# 10LA_org_4PxU_RPi.net
KiCad netlist of a schematic drawn in EAGLE
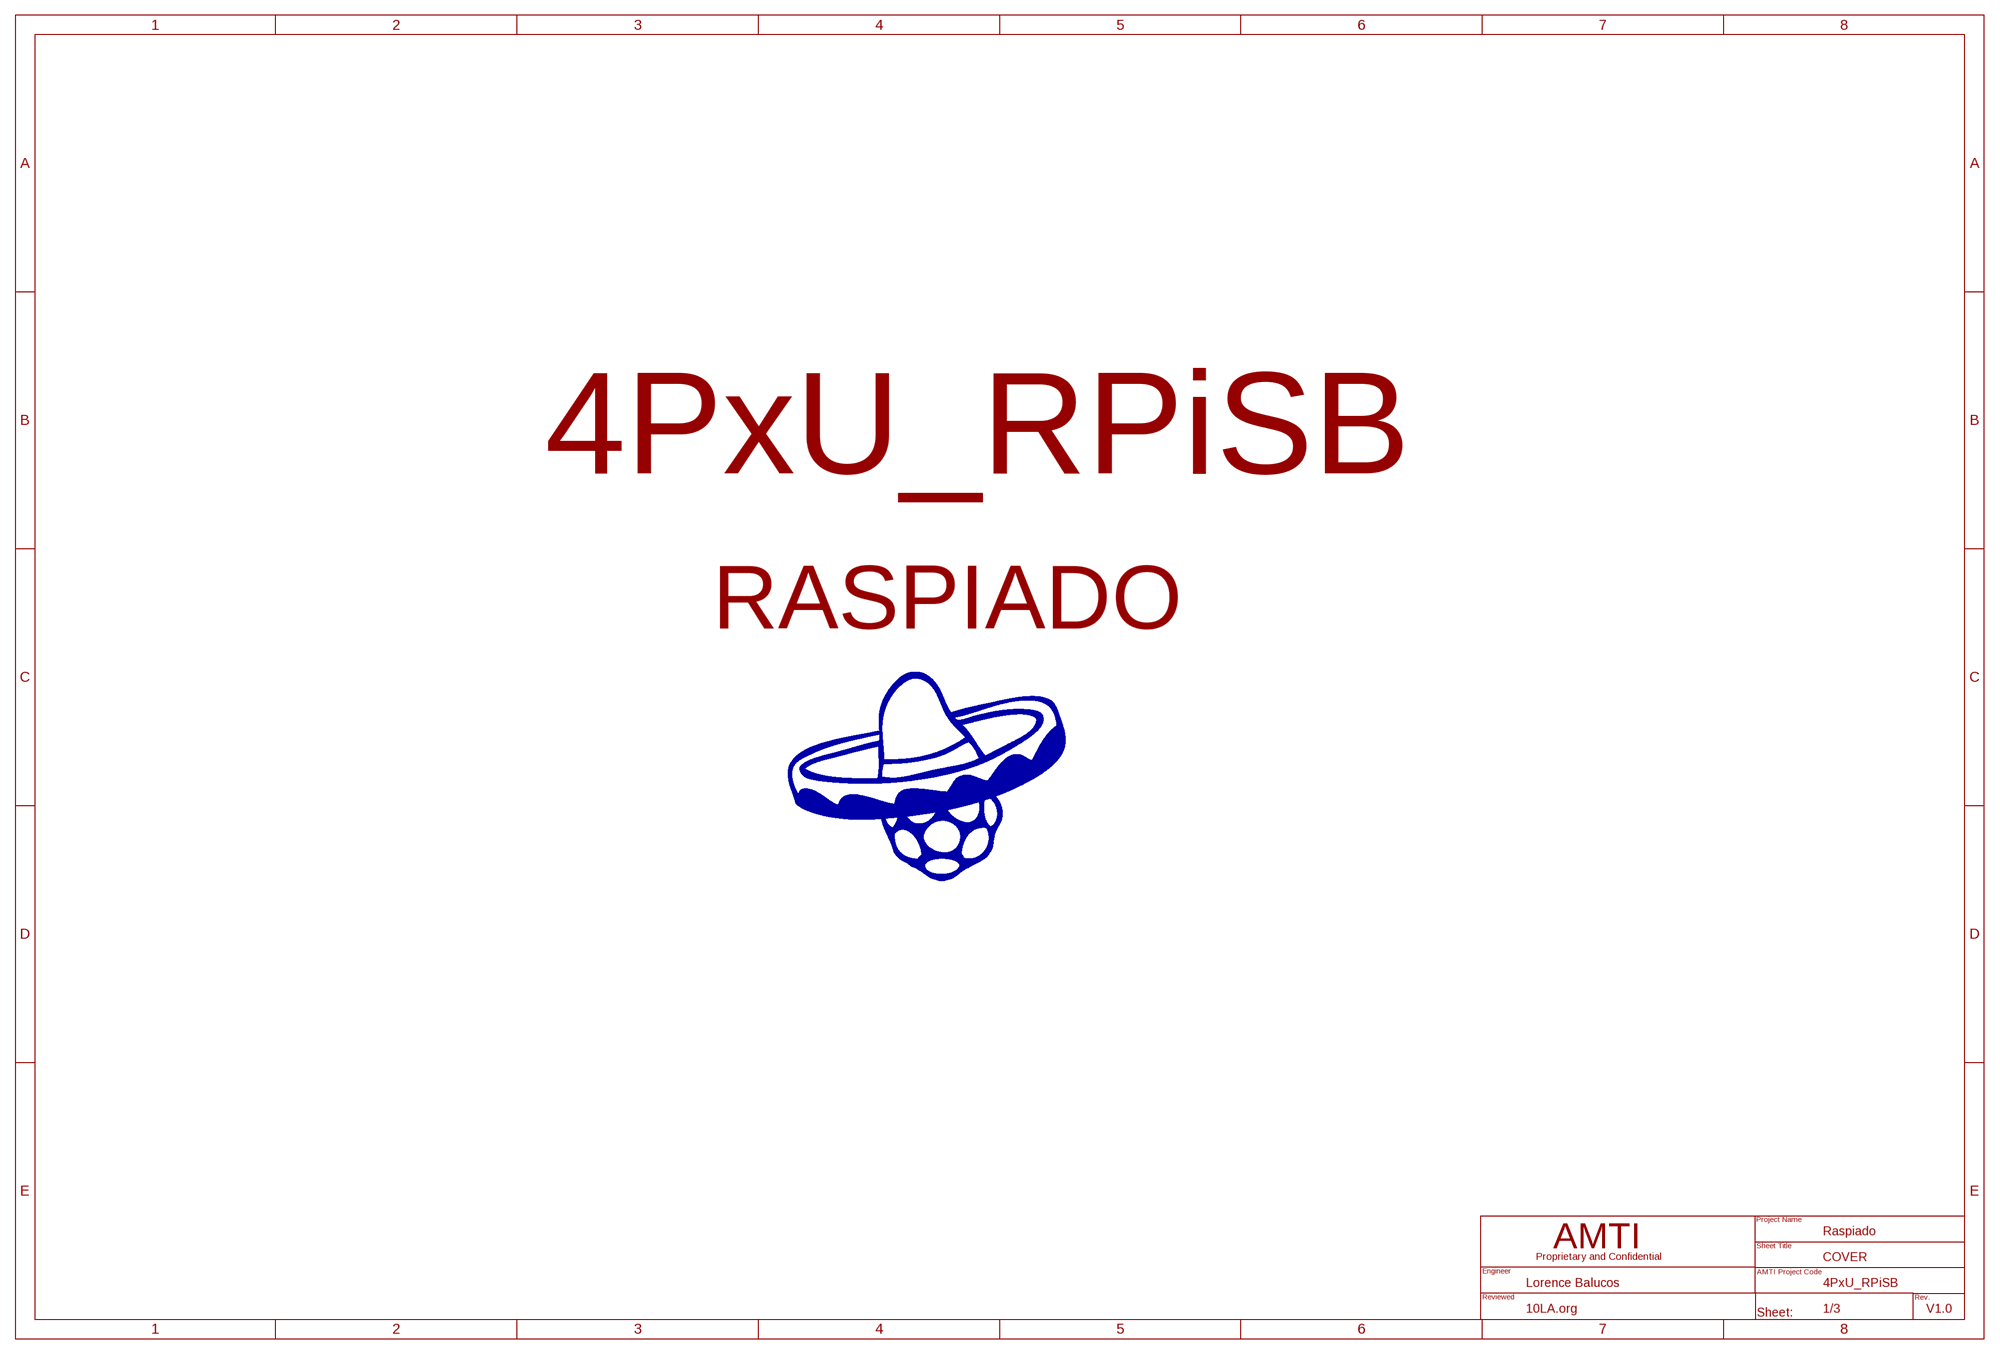
[diagram p0: schematic, sheet 1]
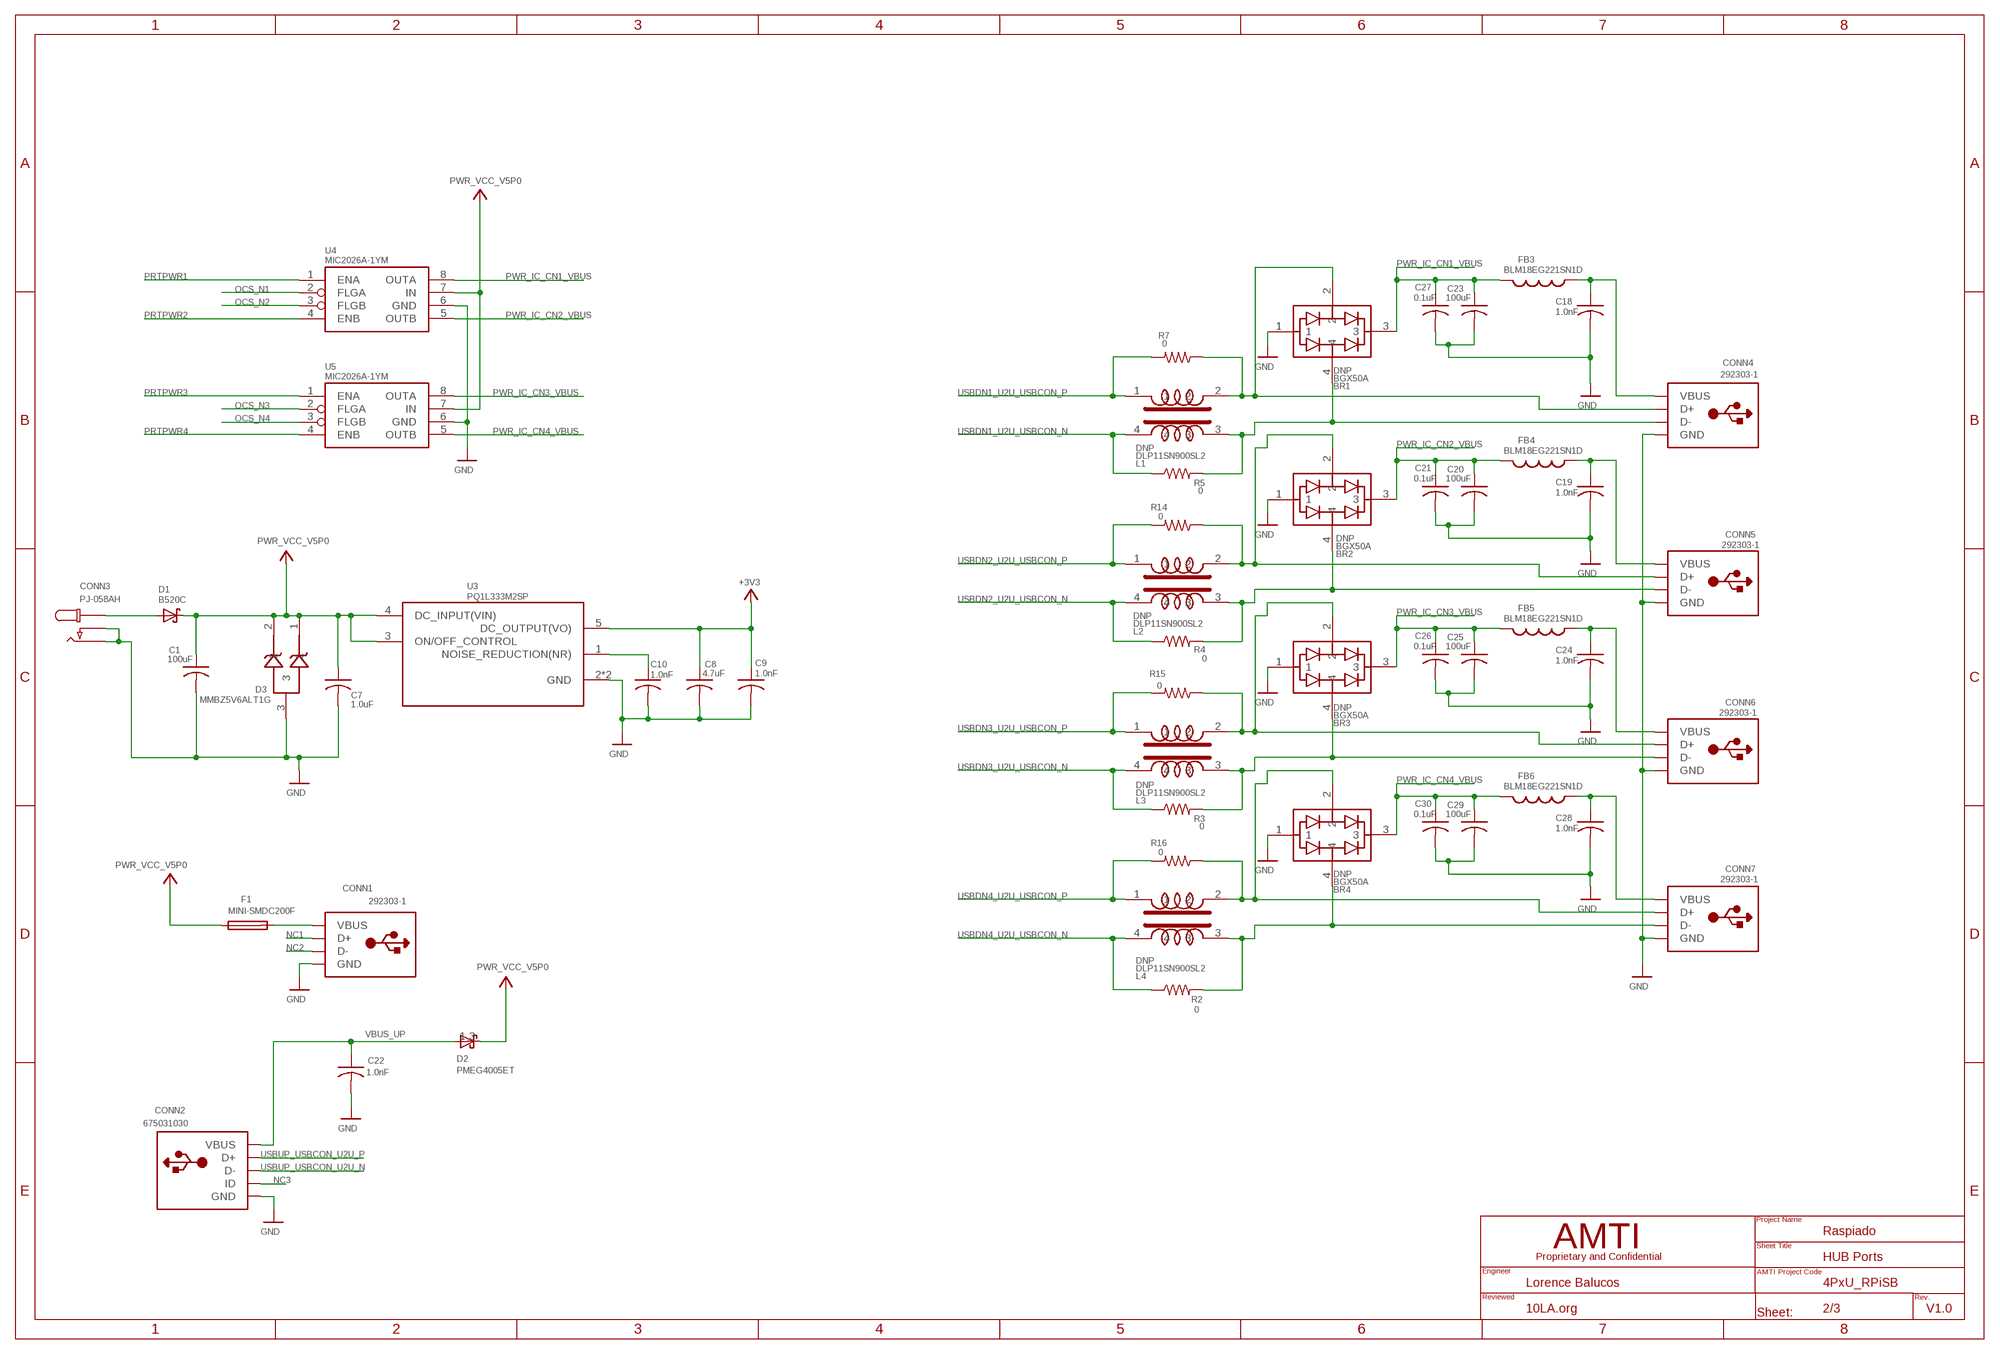
[diagram p1: schematic, sheet 2]
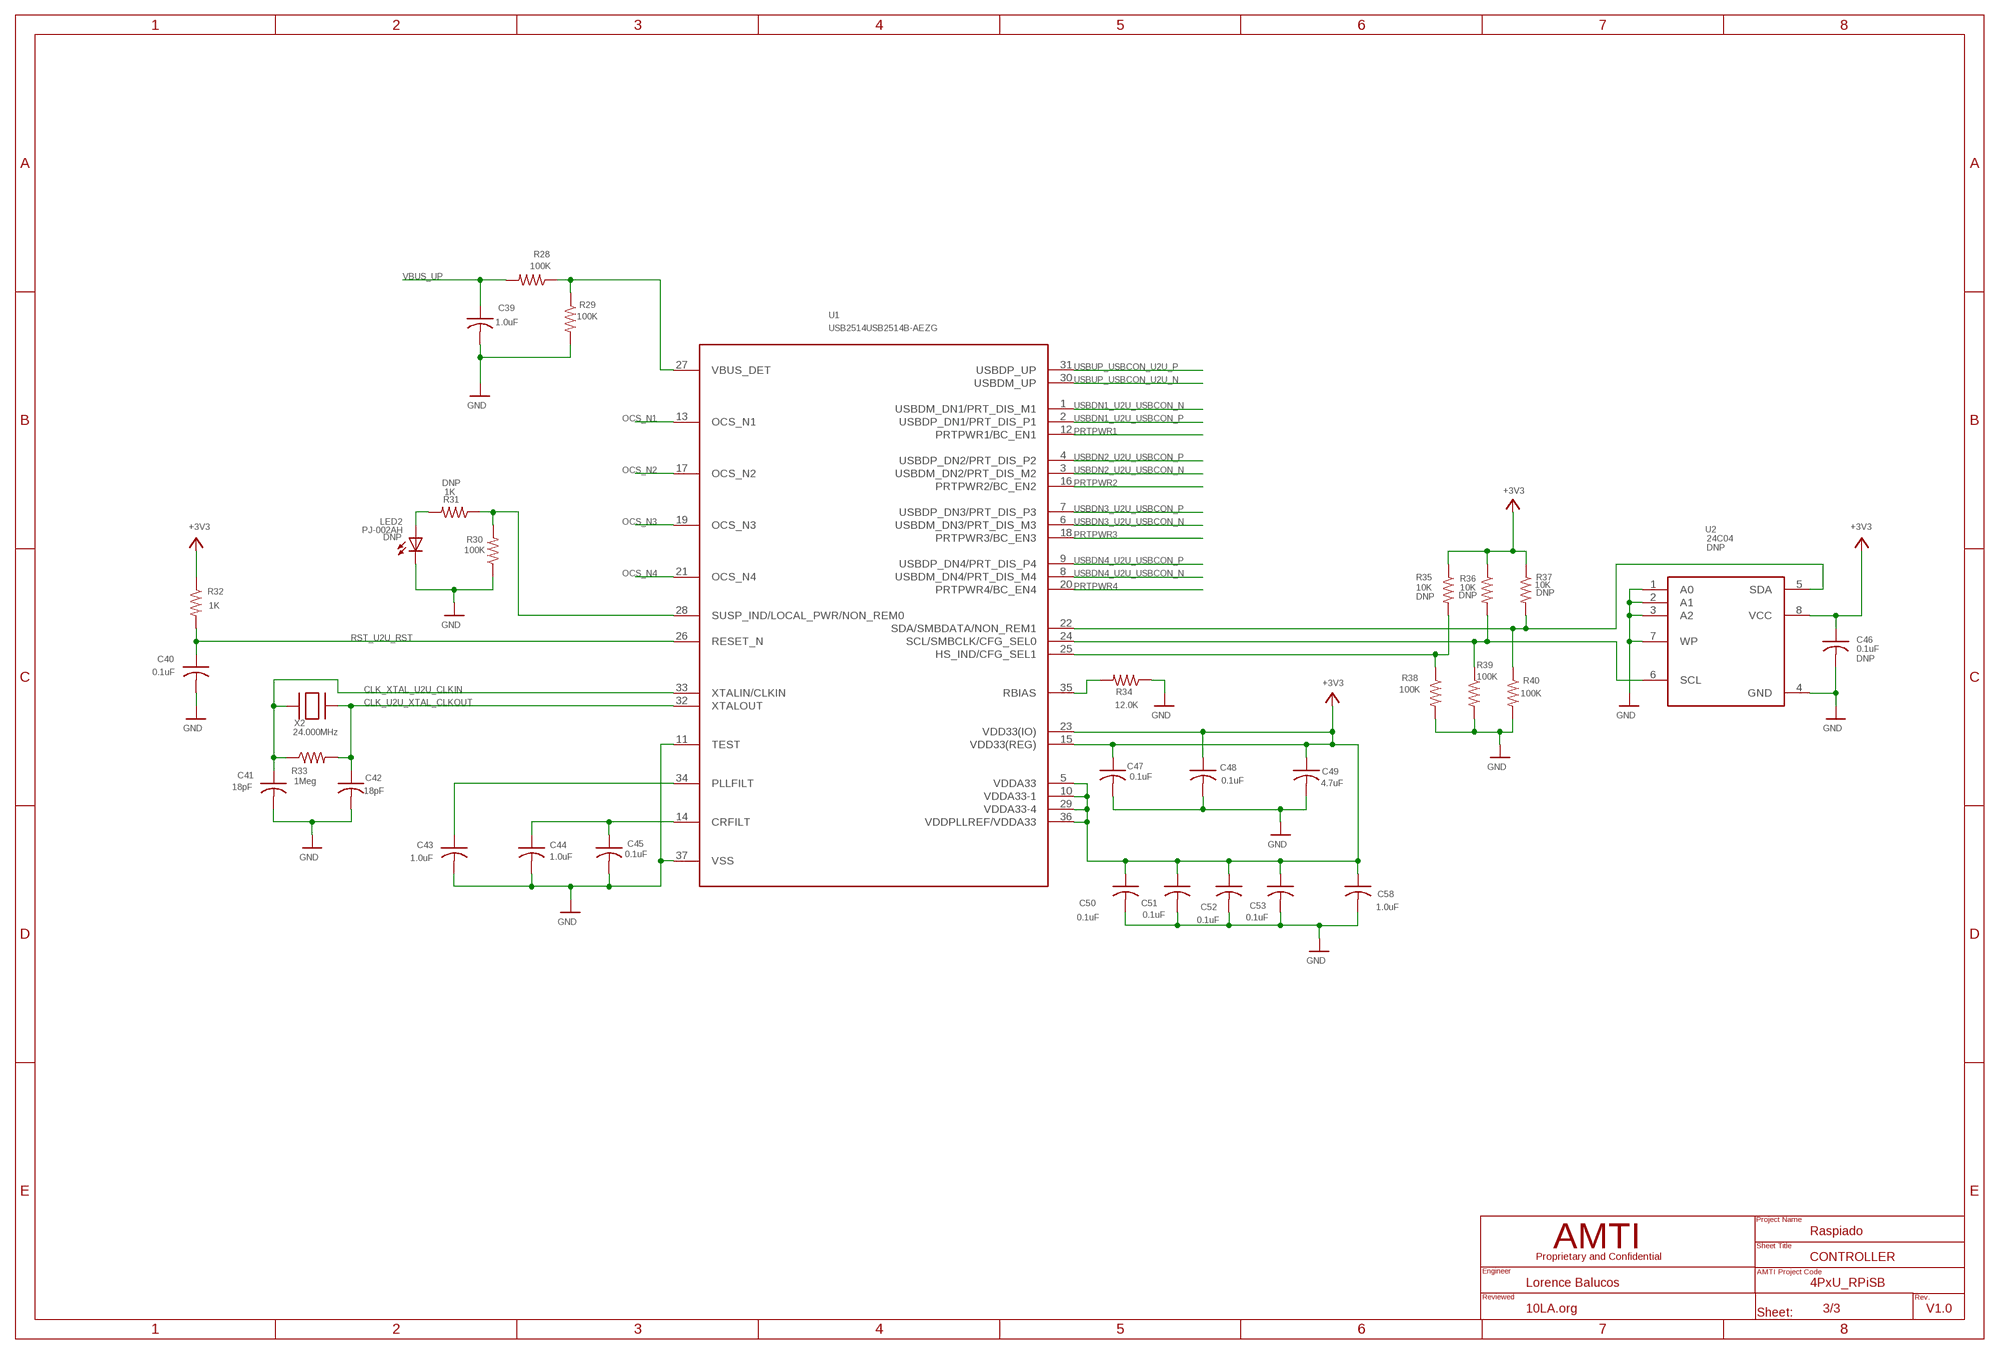
[diagram p2: schematic, sheet 3]

(export (version "E")
  (design (tool "Eeschema 10.0.6"))
  (components
    (comp (ref "BR1")
      (value "BGX50A")
      (footprint "eagle-import:SOT-143")
      (description "Diode, Bridge, Switching, 50v, 140mA, KCAC, SOT-143")
      (fields (field (name "LOAD_OPTION") "DNP"))
      (libsource (lib "eagle-import") (part "BGX50A"))
    )
    (comp (ref "BR2")
      (value "BGX50A")
      (footprint "eagle-import:SOT-143")
      (description "Diode, Bridge, Switching, 50v, 140mA, KCAC, SOT-143")
      (fields (field (name "LOAD_OPTION") "DNP"))
      (libsource (lib "eagle-import") (part "BGX50A"))
    )
    (comp (ref "BR3")
      (value "BGX50A")
      (footprint "eagle-import:SOT-143")
      (description "Diode, Bridge, Switching, 50v, 140mA, KCAC, SOT-143")
      (fields (field (name "LOAD_OPTION") "DNP"))
      (libsource (lib "eagle-import") (part "BGX50A"))
    )
    (comp (ref "BR4")
      (value "BGX50A")
      (footprint "eagle-import:SOT-143")
      (description "Diode, Bridge, Switching, 50v, 140mA, KCAC, SOT-143")
      (fields (field (name "LOAD_OPTION") "DNP"))
      (libsource (lib "eagle-import") (part "BGX50A"))
    )
    (comp (ref "C1")
      (value "100uF")
      (footprint "eagle-import:RADIAL_SMT")
      (description "Capacitor, Low ESR, 100uF, 6.3VDC, 20%, Aluminum, Radial-SMT, 5mm x 5.8mm")
      (libsource (lib "eagle-import") (part "EMZA6R3ADA101ME61G"))
    )
    (comp (ref "C7")
      (value "1.0uF")
      (footprint "eagle-import:C0603")
      (description "Capacitor, 1.0uF, 10%, 6.3V, X5R, 0603")
      (libsource (lib "eagle-import") (part "C-USC0603"))
    )
    (comp (ref "C8")
      (value "4.7uF")
      (footprint "eagle-import:C0603")
      (description "Capacitor, 4.7uF, 6.3VDC, 20%, X5R, 0603")
      (libsource (lib "eagle-import") (part "C-USC0603"))
    )
    (comp (ref "C9")
      (value "1.0nF")
      (footprint "eagle-import:0402")
      (description "Capacitor, 1.0nF, 50VDC, 5%, Standard, 0402")
      (libsource (lib "eagle-import") (part "C-USC0402"))
    )
    (comp (ref "C10")
      (value "1.0nF")
      (footprint "eagle-import:0402")
      (description "Capacitor, 1.0nF, 50VDC, 5%, Standard, 0402")
      (libsource (lib "eagle-import") (part "C-USC0402"))
    )
    (comp (ref "C18")
      (value "1.0nF")
      (footprint "eagle-import:0402")
      (description "Capacitor, 1.0nF, 50VDC, 5%, Standard, 0402")
      (libsource (lib "eagle-import") (part "C-USC0402"))
    )
    (comp (ref "C19")
      (value "1.0nF")
      (footprint "eagle-import:0402")
      (description "Capacitor, 1.0nF, 50VDC, 5%, Standard, 0402")
      (libsource (lib "eagle-import") (part "C-USC0402"))
    )
    (comp (ref "C20")
      (value "100uF")
      (footprint "eagle-import:RADIAL_SMT")
      (description "Capacitor, Low ESR, 100uF, 6.3VDC, 20%, Aluminum, Radial-SMT, 5mm x 5.8mm")
      (libsource (lib "eagle-import") (part "EMZA6R3ADA101ME61G"))
    )
    (comp (ref "C21")
      (value "0.1uF")
      (footprint "eagle-import:0402")
      (description "Capacitor, 0.1uF, 6.3V, 10%, X5R, 0402")
      (libsource (lib "eagle-import") (part "C-USC0402"))
    )
    (comp (ref "C22")
      (value "1.0nF")
      (footprint "eagle-import:0402")
      (description "Capacitor, 1.0nF, 50VDC, 5%, Standard, 0402")
      (libsource (lib "eagle-import") (part "C-USC0402"))
    )
    (comp (ref "C23")
      (value "100uF")
      (footprint "eagle-import:RADIAL_SMT")
      (description "Capacitor, Low ESR, 100uF, 6.3VDC, 20%, Aluminum, Radial-SMT, 5mm x 5.8mm")
      (libsource (lib "eagle-import") (part "EMZA6R3ADA101ME61G"))
    )
    (comp (ref "C24")
      (value "1.0nF")
      (footprint "eagle-import:0402")
      (description "Capacitor, 1.0nF, 50VDC, 5%, Standard, 0402")
      (libsource (lib "eagle-import") (part "C-USC0402"))
    )
    (comp (ref "C25")
      (value "100uF")
      (footprint "eagle-import:RADIAL_SMT")
      (description "Capacitor, Low ESR, 100uF, 6.3VDC, 20%, Aluminum, Radial-SMT, 5mm x 5.8mm")
      (libsource (lib "eagle-import") (part "EMZA6R3ADA101ME61G"))
    )
    (comp (ref "C26")
      (value "0.1uF")
      (footprint "eagle-import:0402")
      (description "Capacitor, 0.1uF, 6.3V, 10%, X5R, 0402")
      (libsource (lib "eagle-import") (part "C-USC0402"))
    )
    (comp (ref "C27")
      (value "0.1uF")
      (footprint "eagle-import:0402")
      (description "Capacitor, 0.1uF, 6.3V, 10%, X5R, 0402")
      (libsource (lib "eagle-import") (part "C-USC0402"))
    )
    (comp (ref "C28")
      (value "1.0nF")
      (footprint "eagle-import:0402")
      (description "Capacitor, 1.0nF, 50VDC, 5%, Standard, 0402")
      (libsource (lib "eagle-import") (part "C-USC0402"))
    )
    (comp (ref "C29")
      (value "100uF")
      (footprint "eagle-import:RADIAL_SMT")
      (description "Capacitor, Low ESR, 100uF, 6.3VDC, 20%, Aluminum, Radial-SMT, 5mm x 5.8mm")
      (libsource (lib "eagle-import") (part "EMZA6R3ADA101ME61G"))
    )
    (comp (ref "C30")
      (value "0.1uF")
      (footprint "eagle-import:0402")
      (description "Capacitor, 0.1uF, 6.3V, 10%, X5R, 0402")
      (libsource (lib "eagle-import") (part "C-USC0402"))
    )
    (comp (ref "CONN1")
      (value "292303-1")
      (footprint "eagle-import:STYLEA,RIGHTANGLE,THROUGH-HOLE")
      (description "Connector, USB, Style A, Right Angle, Through-hole")
      (libsource (lib "eagle-import") (part "USB_292303-1"))
    )
    (comp (ref "CONN2")
      (value "675031030")
      (footprint "eagle-import:MINI_B")
      (description "Connector, 675031030-USB_MINI-B")
      (libsource (lib "eagle-import") (part "675031030-USB_MINI-B"))
    )
    (comp (ref "CONN3")
      (value "PJ-058AH")
      (footprint "eagle-import:PJ-058AH")
      (libsource (lib "eagle-import") (part "PJ-058AH"))
    )
    (comp (ref "CONN4")
      (value "292303-1")
      (footprint "eagle-import:STYLEA,RIGHTANGLE,THROUGH-HOLE")
      (description "Connector, USB, Style A, Right Angle, Through-hole")
      (libsource (lib "eagle-import") (part "USB_292303-1"))
    )
    (comp (ref "CONN5")
      (value "292303-1")
      (footprint "eagle-import:STYLEA,RIGHTANGLE,THROUGH-HOLE")
      (description "Connector, USB, Style A, Right Angle, Through-hole")
      (libsource (lib "eagle-import") (part "USB_292303-1"))
    )
    (comp (ref "CONN6")
      (value "292303-1")
      (footprint "eagle-import:STYLEA,RIGHTANGLE,THROUGH-HOLE")
      (description "Connector, USB, Style A, Right Angle, Through-hole")
      (libsource (lib "eagle-import") (part "USB_292303-1"))
    )
    (comp (ref "CONN7")
      (value "292303-1")
      (footprint "eagle-import:STYLEA,RIGHTANGLE,THROUGH-HOLE")
      (description "Connector, USB, Style A, Right Angle, Through-hole")
      (libsource (lib "eagle-import") (part "USB_292303-1"))
    )
    (comp (ref "D1")
      (value "B520C")
      (footprint "eagle-import:B520C")
      (description "Diode, 5.0A SURFACE MOUNT SCHOTTKY BARRIER RECTIFIER")
      (libsource (lib "eagle-import") (part "B520C"))
    )
    (comp (ref "D2")
      (value "PMEG4005ET")
      (footprint "eagle-import:SOT23")
      (description "Diode ,0.5 A,MEGA Schottky barrier rectifiers,SOT23")
      (libsource (lib "eagle-import") (part "PMEG4005ET"))
    )
    (comp (ref "D3")
      (value "MMBZ5V6ALT1G")
      (footprint "eagle-import:SOT23")
      (description "Diode, TVS, Arrays 5.6V 225mW Dual Common Anode")
      (libsource (lib "eagle-import") (part "MMBZ_ALT1G"))
    )
    (comp (ref "F1")
      (value "MINI-SMDC200F")
      (footprint "eagle-import:MINI-SMDC200F")
      (description "Fuse, PPTC 2A 8V 100A")
      (libsource (lib "eagle-import") (part "MINI-SMDC-200F"))
    )
    (comp (ref "FB3")
      (value "BLM18EG221SN1D")
      (footprint "eagle-import:C0603")
      (description "Ferrite Bead, 220 Ohm, 2A, 0.05DCR, 0603")
      (libsource (lib "eagle-import") (part "BLM18EG221SN1D"))
    )
    (comp (ref "FB4")
      (value "BLM18EG221SN1D")
      (footprint "eagle-import:C0603")
      (description "Ferrite Bead, 220 Ohm, 2A, 0.05DCR, 0603")
      (libsource (lib "eagle-import") (part "BLM18EG221SN1D"))
    )
    (comp (ref "FB5")
      (value "BLM18EG221SN1D")
      (footprint "eagle-import:C0603")
      (description "Ferrite Bead, 220 Ohm, 2A, 0.05DCR, 0603")
      (libsource (lib "eagle-import") (part "BLM18EG221SN1D"))
    )
    (comp (ref "FB6")
      (value "BLM18EG221SN1D")
      (footprint "eagle-import:C0603")
      (description "Ferrite Bead, 220 Ohm, 2A, 0.05DCR, 0603")
      (libsource (lib "eagle-import") (part "BLM18EG221SN1D"))
    )
    (comp (ref "L1")
      (value "DLP11SN900SL2")
      (footprint "eagle-import:0504")
      (description "Inductor, Common Mode Choke, DLP11SN900SL2, 0504")
      (fields (field (name "LOAD_OPTION") "DNP"))
      (libsource (lib "eagle-import") (part "DLP11SN900SL2"))
    )
    (comp (ref "L2")
      (value "DLP11SN900SL2")
      (footprint "eagle-import:0504")
      (description "Inductor, Common Mode Choke, DLP11SN900SL2, 0504")
      (fields (field (name "LOAD_OPTION") "DNP"))
      (libsource (lib "eagle-import") (part "DLP11SN900SL2"))
    )
    (comp (ref "L3")
      (value "DLP11SN900SL2")
      (footprint "eagle-import:0504")
      (description "Inductor, Common Mode Choke, DLP11SN900SL2, 0504")
      (fields (field (name "LOAD_OPTION") "DNP"))
      (libsource (lib "eagle-import") (part "DLP11SN900SL2"))
    )
    (comp (ref "L4")
      (value "DLP11SN900SL2")
      (footprint "eagle-import:0504")
      (description "Inductor, Common Mode Choke, DLP11SN900SL2, 0504")
      (fields (field (name "LOAD_OPTION") "DNP"))
      (libsource (lib "eagle-import") (part "DLP11SN900SL2"))
    )
    (comp (ref "R2")
      (value "0")
      (footprint "eagle-import:R0402")
      (description "Resistor, 0ohm,0402")
      (libsource (lib "eagle-import") (part "R-US_R0402"))
    )
    (comp (ref "R3")
      (value "0")
      (footprint "eagle-import:R0402")
      (description "Resistor, 0ohm,0402")
      (libsource (lib "eagle-import") (part "R-US_R0402"))
    )
    (comp (ref "R4")
      (value "0")
      (footprint "eagle-import:R0402")
      (description "Resistor, 0ohm,0402")
      (libsource (lib "eagle-import") (part "R-US_R0402"))
    )
    (comp (ref "R5")
      (value "0")
      (footprint "eagle-import:R0402")
      (description "Resistor, 0ohm,0402")
      (libsource (lib "eagle-import") (part "R-US_R0402"))
    )
    (comp (ref "R7")
      (value "0")
      (footprint "eagle-import:R0402")
      (description "Resistor, 0ohm,0402")
      (libsource (lib "eagle-import") (part "R-US_R0402"))
    )
    (comp (ref "R14")
      (value "0")
      (footprint "eagle-import:R0402")
      (description "Resistor, 0ohm,0402")
      (libsource (lib "eagle-import") (part "R-US_R0402"))
    )
    (comp (ref "R15")
      (value "0")
      (footprint "eagle-import:R0402")
      (description "Resistor, 0ohm,0402")
      (libsource (lib "eagle-import") (part "R-US_R0402"))
    )
    (comp (ref "R16")
      (value "0")
      (footprint "eagle-import:R0402")
      (description "Resistor, 0ohm,0402")
      (libsource (lib "eagle-import") (part "R-US_R0402"))
    )
    (comp (ref "U3")
      (value "PQ1L333M2SP")
      (footprint "eagle-import:PQ1L333M2SP")
      (description "IC, PQ1L333M2SP, Voltage Regulator, 3.3V, 300mA, Low Dropout, 900mW, SOT-89-5")
      (libsource (lib "eagle-import") (part "PQ1L333M2SP"))
    )
    (comp (ref "U4")
      (value "MIC2026A-1YM")
      (footprint "eagle-import:SO_08")
      (description "IC, MIC2026A-1YM, Power Distribution Switch, SO-8")
      (libsource (lib "eagle-import") (part "MIC2026-1YMA"))
    )
    (comp (ref "U5")
      (value "MIC2026A-1YM")
      (footprint "eagle-import:SO_08")
      (description "IC, MIC2026A-1YM, Power Distribution Switch, SO-8")
      (libsource (lib "eagle-import") (part "MIC2026-1YMA"))
    )
    (comp (ref "C39")
      (value "1.0uF")
      (footprint "eagle-import:C0603")
      (description "Capacitor, 1.0uF, 10%, 6.3V, X5R, 0603")
      (libsource (lib "eagle-import") (part "C-USC0603"))
    )
    (comp (ref "C40")
      (value "0.1uF")
      (footprint "eagle-import:0402")
      (description "Capacitor, 0.1uF, 6.3V, 10%, X5R, 0402")
      (libsource (lib "eagle-import") (part "C-USC0402"))
    )
    (comp (ref "C41")
      (value "18pF")
      (footprint "eagle-import:0402")
      (description "Capacitor, 18pF, 50V, 5%, NPO, 0402")
      (libsource (lib "eagle-import") (part "C-USC0402"))
    )
    (comp (ref "C42")
      (value "18pF")
      (footprint "eagle-import:0402")
      (description "Capacitor, 18pF, 50V, 5%, NPO, 0402")
      (libsource (lib "eagle-import") (part "C-USC0402"))
    )
    (comp (ref "C43")
      (value "1.0uF")
      (footprint "eagle-import:0402")
      (description "Capacitor, 1.0uF, 10%, 6.3V, X5R, 0603")
      (libsource (lib "eagle-import") (part "C-USC0402"))
    )
    (comp (ref "C44")
      (value "1.0uF")
      (footprint "eagle-import:0402")
      (description "Capacitor, 1.0uF, 10%, 6.3V, X5R, 0603")
      (libsource (lib "eagle-import") (part "C-USC0402"))
    )
    (comp (ref "C45")
      (value "0.1uF")
      (footprint "eagle-import:0402")
      (description "Capacitor, 0.1uF, 6.3V, 10%, X5R, 0402")
      (libsource (lib "eagle-import") (part "C-USC0402"))
    )
    (comp (ref "C46")
      (value "0.1uF")
      (footprint "eagle-import:0402")
      (description "Capacitor, 0.1uF, 6.3V, 10%, X5R, 0402")
      (fields (field (name "LOAD_OPTION") "DNP"))
      (libsource (lib "eagle-import") (part "C-USC0402"))
    )
    (comp (ref "C47")
      (value "0.1uF")
      (footprint "eagle-import:0402")
      (description "Capacitor, 0.1uF, 6.3V, 10%, X5R, 0402")
      (libsource (lib "eagle-import") (part "C-USC0402"))
    )
    (comp (ref "C48")
      (value "0.1uF")
      (footprint "eagle-import:0402")
      (description "Capacitor, 0.1uF, 6.3V, 10%, X5R, 0402")
      (libsource (lib "eagle-import") (part "C-USC0402"))
    )
    (comp (ref "C49")
      (value "4.7uF")
      (footprint "eagle-import:C0603")
      (description "Capacitor, 4.7uF, 6.3VDC, 20%, X5R, 0603")
      (libsource (lib "eagle-import") (part "C-USC0603"))
    )
    (comp (ref "C50")
      (value "0.1uF")
      (footprint "eagle-import:0402")
      (description "Capacitor, 0.1uF, 6.3V, 10%, X5R, 0402")
      (libsource (lib "eagle-import") (part "C-USC0402"))
    )
    (comp (ref "C51")
      (value "0.1uF")
      (footprint "eagle-import:0402")
      (description "Capacitor, 0.1uF, 6.3V, 10%, X5R, 0402")
      (libsource (lib "eagle-import") (part "C-USC0402"))
    )
    (comp (ref "C52")
      (value "0.1uF")
      (footprint "eagle-import:0402")
      (description "Capacitor, 0.1uF, 6.3V, 10%, X5R, 0402")
      (libsource (lib "eagle-import") (part "C-USC0402"))
    )
    (comp (ref "C53")
      (value "0.1uF")
      (footprint "eagle-import:0402")
      (description "Capacitor, 0.1uF, 6.3V, 10%, X5R, 0402")
      (libsource (lib "eagle-import") (part "C-USC0402"))
    )
    (comp (ref "C58")
      (value "1.0uF")
      (footprint "eagle-import:C0603")
      (description "Capacitor, 1.0uF, 10%, 6.3V, X5R, 0603")
      (libsource (lib "eagle-import") (part "C-USC0603"))
    )
    (comp (ref "LED2")
      (value "PJ-002AH")
      (footprint "eagle-import:0603")
      (description "LED, CHIPLED 0603")
      (fields (field (name "LOAD_OPTION") "DNP"))
      (libsource (lib "eagle-import") (part "LEDCHIPLED_0603"))
    )
    (comp (ref "R28")
      (value "100K")
      (footprint "eagle-import:R0603")
      (description "Resistor, 100K, 5%, 1/16W, 0603")
      (libsource (lib "eagle-import") (part "R-US_R0603"))
    )
    (comp (ref "R29")
      (value "100K")
      (footprint "eagle-import:R0603")
      (description "Resistor, 100K, 5%, 1/16W, 0603")
      (libsource (lib "eagle-import") (part "R-US_R0603"))
    )
    (comp (ref "R30")
      (value "100K")
      (footprint "eagle-import:R0603")
      (description "Resistor, 100K, 5%, 1/16W, 0603")
      (libsource (lib "eagle-import") (part "R-US_R0603"))
    )
    (comp (ref "R31")
      (value "1K")
      (footprint "eagle-import:R0603")
      (description "Resistor, 1K, 5%, 1/16W, 0603")
      (fields (field (name "LOAD_OPTION") "DNP"))
      (libsource (lib "eagle-import") (part "R-US_R0603"))
    )
    (comp (ref "R32")
      (value "1K")
      (footprint "eagle-import:R0603")
      (description "Resistor, 1K, 5%, 1/16W, 0603")
      (libsource (lib "eagle-import") (part "R-US_R0603"))
    )
    (comp (ref "R33")
      (value "1Meg")
      (footprint "eagle-import:R0603")
      (description "Resistor, 1Meg, 5%, 1/16W, 0603")
      (libsource (lib "eagle-import") (part "R-US_R0603"))
    )
    (comp (ref "R34")
      (value "12.0K")
      (footprint "eagle-import:R0603")
      (description "Resistor, 12.0K, 1%, 1/16W, 0603")
      (libsource (lib "eagle-import") (part "R-US_R0603"))
    )
    (comp (ref "R35")
      (value "10K")
      (footprint "eagle-import:R0603")
      (description "Resistor, 10.0K, 1%, 1/16W, 0603")
      (fields (field (name "LOAD_OPTION") "DNP"))
      (libsource (lib "eagle-import") (part "R-US_R0603"))
    )
    (comp (ref "R36")
      (value "10K")
      (footprint "eagle-import:R0603")
      (description "Resistor, 10.0K, 1%, 1/16W, 0603")
      (fields (field (name "LOAD_OPTION") "DNP"))
      (libsource (lib "eagle-import") (part "R-US_R0603"))
    )
    (comp (ref "R37")
      (value "10K")
      (footprint "eagle-import:R0603")
      (description "Resistor, 10.0K, 1%, 1/16W, 0603")
      (fields (field (name "LOAD_OPTION") "DNP"))
      (libsource (lib "eagle-import") (part "R-US_R0603"))
    )
    (comp (ref "R38")
      (value "100K")
      (footprint "eagle-import:R0603")
      (description "Resistor, 100K, 5%, 1/16W, 0603")
      (libsource (lib "eagle-import") (part "R-US_R0603"))
    )
    (comp (ref "R39")
      (value "100K")
      (footprint "eagle-import:R0603")
      (description "Resistor, 100K, 5%, 1/16W, 0603")
      (libsource (lib "eagle-import") (part "R-US_R0603"))
    )
    (comp (ref "R40")
      (value "100K")
      (footprint "eagle-import:R0603")
      (description "Resistor, 100K, 5%, 1/16W, 0603")
      (libsource (lib "eagle-import") (part "R-US_R0603"))
    )
    (comp (ref "U1")
      (value "USB2514USB2514B-AEZG")
      (footprint "eagle-import:QFN36")
      (description "IC, USB2514B, 4 Port USB 2.0 Hub, QFN36")
      (libsource (lib "eagle-import") (part "USB2514USB2514B-AEZG"))
    )
    (comp (ref "U2")
      (value "24C04")
      (footprint "eagle-import:SO-8")
      (description "IC, EEPROM,3V to 5.5V for ST24x04,")
      (fields (field (name "LOAD_OPTION") "DNP"))
      (libsource (lib "eagle-import") (part "24C04"))
    )
    (comp (ref "X2")
      (value "24.000MHz")
      (footprint "eagle-import:HC-49SMT")
      (description "Crystal, 24.000MHz, 50ppm, 18pF, HC-49SMT")
      (libsource (lib "eagle-import") (part "HCM49-24.000MABJ-UT"))
    )
  )
  (nets
    (net (code "1") (name "+3V3") (class "Default")
      (node (ref "C46") (pin "1") (pinfunction "1_1") (pintype "passive"))
      (node (ref "C47") (pin "1") (pinfunction "1_1") (pintype "passive"))
      (node (ref "C48") (pin "1") (pinfunction "1_1") (pintype "passive"))
      (node (ref "C49") (pin "1") (pinfunction "1_1") (pintype "passive"))
      (node (ref "C50") (pin "1") (pinfunction "1_1") (pintype "passive"))
      (node (ref "C51") (pin "1") (pinfunction "1_1") (pintype "passive"))
      (node (ref "C52") (pin "1") (pinfunction "1_1") (pintype "passive"))
      (node (ref "C53") (pin "1") (pinfunction "1_1") (pintype "passive"))
      (node (ref "C58") (pin "1") (pinfunction "1_1") (pintype "passive"))
      (node (ref "C8") (pin "1") (pinfunction "1_1") (pintype "passive"))
      (node (ref "C9") (pin "1") (pinfunction "1_1") (pintype "passive"))
      (node (ref "R32") (pin "1") (pinfunction "1_1") (pintype "passive"))
      (node (ref "R35") (pin "1") (pinfunction "1_1") (pintype "passive"))
      (node (ref "R36") (pin "1") (pinfunction "1_1") (pintype "passive"))
      (node (ref "R37") (pin "1") (pinfunction "1_1") (pintype "passive"))
      (node (ref "U1") (pin "10") (pinfunction "VDDA33-1_10") (pintype "bidirectional"))
      (node (ref "U1") (pin "15") (pinfunction "VDD33(REG)_15") (pintype "bidirectional"))
      (node (ref "U1") (pin "23") (pinfunction "VDD33(IO)_23") (pintype "bidirectional"))
      (node (ref "U1") (pin "29") (pinfunction "VDDA33-4_29") (pintype "bidirectional"))
      (node (ref "U1") (pin "36") (pinfunction "VDDPLLREF/VDDA33_36") (pintype "bidirectional"))
      (node (ref "U1") (pin "5") (pinfunction "VDDA33_5") (pintype "bidirectional"))
      (node (ref "U2") (pin "8") (pinfunction "VCC_8") (pintype "bidirectional"))
      (node (ref "U3") (pin "5") (pinfunction "DC_OUTPUT(VO)_5") (pintype "bidirectional"))
    )
    (net (code "2") (name "CLK_U2U_XTAL_CLKOUT") (class "Default")
      (node (ref "C42") (pin "1") (pinfunction "1_1") (pintype "passive"))
      (node (ref "R33") (pin "2") (pinfunction "2_2") (pintype "passive"))
      (node (ref "U1") (pin "32") (pinfunction "XTALOUT_32") (pintype "bidirectional"))
      (node (ref "X2") (pin "2") (pinfunction "P$2_2") (pintype "bidirectional"))
    )
    (net (code "3") (name "CLK_XTAL_U2U_CLKIN") (class "Default")
      (node (ref "C41") (pin "1") (pinfunction "1_1") (pintype "passive"))
      (node (ref "R33") (pin "1") (pinfunction "1_1") (pintype "passive"))
      (node (ref "U1") (pin "33") (pinfunction "XTALIN/CLKIN_33") (pintype "bidirectional"))
      (node (ref "X2") (pin "1") (pinfunction "P$1_1") (pintype "bidirectional"))
    )
    (net (code "4") (name "GND") (class "Default")
      (node (ref "BR1") (pin "1") (pinfunction "1_1") (pintype "bidirectional"))
      (node (ref "BR2") (pin "1") (pinfunction "1_1") (pintype "bidirectional"))
      (node (ref "BR3") (pin "1") (pinfunction "1_1") (pintype "bidirectional"))
      (node (ref "BR4") (pin "1") (pinfunction "1_1") (pintype "bidirectional"))
      (node (ref "C1") (pin "-") (pinfunction "2_-") (pintype "passive"))
      (node (ref "C10") (pin "2") (pinfunction "2_2") (pintype "passive"))
      (node (ref "C18") (pin "2") (pinfunction "2_2") (pintype "passive"))
      (node (ref "C19") (pin "2") (pinfunction "2_2") (pintype "passive"))
      (node (ref "C20") (pin "-") (pinfunction "2_-") (pintype "passive"))
      (node (ref "C21") (pin "2") (pinfunction "2_2") (pintype "passive"))
      (node (ref "C22") (pin "2") (pinfunction "2_2") (pintype "passive"))
      (node (ref "C23") (pin "-") (pinfunction "2_-") (pintype "passive"))
      (node (ref "C24") (pin "2") (pinfunction "2_2") (pintype "passive"))
      (node (ref "C25") (pin "-") (pinfunction "2_-") (pintype "passive"))
      (node (ref "C26") (pin "2") (pinfunction "2_2") (pintype "passive"))
      (node (ref "C27") (pin "2") (pinfunction "2_2") (pintype "passive"))
      (node (ref "C28") (pin "2") (pinfunction "2_2") (pintype "passive"))
      (node (ref "C29") (pin "-") (pinfunction "2_-") (pintype "passive"))
      (node (ref "C30") (pin "2") (pinfunction "2_2") (pintype "passive"))
      (node (ref "C39") (pin "2") (pinfunction "2_2") (pintype "passive"))
      (node (ref "C40") (pin "2") (pinfunction "2_2") (pintype "passive"))
      (node (ref "C41") (pin "2") (pinfunction "2_2") (pintype "passive"))
      (node (ref "C42") (pin "2") (pinfunction "2_2") (pintype "passive"))
      (node (ref "C43") (pin "2") (pinfunction "2_2") (pintype "passive"))
      (node (ref "C44") (pin "2") (pinfunction "2_2") (pintype "passive"))
      (node (ref "C45") (pin "2") (pinfunction "2_2") (pintype "passive"))
      (node (ref "C46") (pin "2") (pinfunction "2_2") (pintype "passive"))
      (node (ref "C47") (pin "2") (pinfunction "2_2") (pintype "passive"))
      (node (ref "C48") (pin "2") (pinfunction "2_2") (pintype "passive"))
      (node (ref "C49") (pin "2") (pinfunction "2_2") (pintype "passive"))
      (node (ref "C50") (pin "2") (pinfunction "2_2") (pintype "passive"))
      (node (ref "C51") (pin "2") (pinfunction "2_2") (pintype "passive"))
      (node (ref "C52") (pin "2") (pinfunction "2_2") (pintype "passive"))
      (node (ref "C53") (pin "2") (pinfunction "2_2") (pintype "passive"))
      (node (ref "C58") (pin "2") (pinfunction "2_2") (pintype "passive"))
      (node (ref "C7") (pin "2") (pinfunction "2_2") (pintype "passive"))
      (node (ref "C8") (pin "2") (pinfunction "2_2") (pintype "passive"))
      (node (ref "C9") (pin "2") (pinfunction "2_2") (pintype "passive"))
      (node (ref "CONN1") (pin "GND") (pinfunction "GND_GND") (pintype "power_in"))
      (node (ref "CONN1") (pin "GND1") (pinfunction "GND_GND1") (pintype "power_in"))
      (node (ref "CONN1") (pin "GND2") (pinfunction "GND_GND2") (pintype "power_in"))
      (node (ref "CONN2") (pin "GND") (pinfunction "GND_GND") (pintype "power_in"))
      (node (ref "CONN2") (pin "GND1") (pinfunction "GND_GND1") (pintype "power_in"))
      (node (ref "CONN2") (pin "GND2") (pinfunction "GND_GND2") (pintype "power_in"))
      (node (ref "CONN2") (pin "GND3") (pinfunction "GND_GND3") (pintype "power_in"))
      (node (ref "CONN2") (pin "GND4") (pinfunction "GND_GND4") (pintype "power_in"))
      (node (ref "CONN3") (pin "2") (pinfunction "2_2") (pintype "bidirectional"))
      (node (ref "CONN3") (pin "3") (pinfunction "3_3") (pintype "bidirectional"))
      (node (ref "CONN4") (pin "GND") (pinfunction "GND_GND") (pintype "power_in"))
      (node (ref "CONN4") (pin "GND1") (pinfunction "GND_GND1") (pintype "power_in"))
      (node (ref "CONN4") (pin "GND2") (pinfunction "GND_GND2") (pintype "power_in"))
      (node (ref "CONN5") (pin "GND") (pinfunction "GND_GND") (pintype "power_in"))
      (node (ref "CONN5") (pin "GND1") (pinfunction "GND_GND1") (pintype "power_in"))
      (node (ref "CONN5") (pin "GND2") (pinfunction "GND_GND2") (pintype "power_in"))
      (node (ref "CONN6") (pin "GND") (pinfunction "GND_GND") (pintype "power_in"))
      (node (ref "CONN6") (pin "GND1") (pinfunction "GND_GND1") (pintype "power_in"))
      (node (ref "CONN6") (pin "GND2") (pinfunction "GND_GND2") (pintype "power_in"))
      (node (ref "CONN7") (pin "GND") (pinfunction "GND_GND") (pintype "power_in"))
      (node (ref "CONN7") (pin "GND1") (pinfunction "GND_GND1") (pintype "power_in"))
      (node (ref "CONN7") (pin "GND2") (pinfunction "GND_GND2") (pintype "power_in"))
      (node (ref "D3") (pin "3") (pinfunction "3_3") (pintype "bidirectional"))
      (node (ref "LED2") (pin "C") (pinfunction "C_C") (pintype "passive"))
      (node (ref "R29") (pin "2") (pinfunction "2_2") (pintype "passive"))
      (node (ref "R30") (pin "1") (pinfunction "1_1") (pintype "passive"))
      (node (ref "R34") (pin "1") (pinfunction "1_1") (pintype "passive"))
      (node (ref "R38") (pin "2") (pinfunction "2_2") (pintype "passive"))
      (node (ref "R39") (pin "2") (pinfunction "2_2") (pintype "passive"))
      (node (ref "R40") (pin "2") (pinfunction "2_2") (pintype "passive"))
      (node (ref "U1") (pin "11") (pinfunction "TEST_11") (pintype "bidirectional"))
      (node (ref "U1") (pin "37") (pinfunction "VSS_37") (pintype "bidirectional"))
      (node (ref "U2") (pin "1") (pinfunction "A0_1") (pintype "bidirectional"))
      (node (ref "U2") (pin "2") (pinfunction "A1_2") (pintype "bidirectional"))
      (node (ref "U2") (pin "3") (pinfunction "A2_3") (pintype "bidirectional"))
      (node (ref "U2") (pin "4") (pinfunction "GND_4") (pintype "bidirectional"))
      (node (ref "U2") (pin "7") (pinfunction "WP_7") (pintype "bidirectional"))
      (node (ref "U3") (pin "2") (pinfunction "GND_2") (pintype "bidirectional"))
      (node (ref "U3") (pin "P$3") (pinfunction "GND_P$3") (pintype "bidirectional"))
      (node (ref "U4") (pin "6") (pinfunction "GND_6") (pintype "power_in"))
      (node (ref "U5") (pin "6") (pinfunction "GND_6") (pintype "power_in"))
    )
    (net (code "5") (name "NC1") (class "Default")
      (node (ref "CONN1") (pin "SIG2") (pinfunction "D+_SIG2") (pintype "bidirectional"))
    )
    (net (code "6") (name "NC2") (class "Default")
      (node (ref "CONN1") (pin "SIG1") (pinfunction "D-_SIG1") (pintype "bidirectional"))
    )
    (net (code "7") (name "NC3") (class "Default")
      (node (ref "CONN2") (pin "ID") (pinfunction "ID_ID") (pintype "bidirectional"))
    )
    (net (code "8") (name "Net-(C18-Pad1)") (class "Default")
      (node (ref "C18") (pin "1") (pinfunction "1_1") (pintype "passive"))
      (node (ref "CONN4") (pin "VBUS") (pinfunction "VBUS_VBUS") (pintype "power_in"))
      (node (ref "FB3") (pin "1") (pinfunction "1_1") (pintype "passive"))
    )
    (net (code "9") (name "Net-(C19-Pad1)") (class "Default")
      (node (ref "C19") (pin "1") (pinfunction "1_1") (pintype "passive"))
      (node (ref "CONN5") (pin "VBUS") (pinfunction "VBUS_VBUS") (pintype "power_in"))
      (node (ref "FB4") (pin "1") (pinfunction "1_1") (pintype "passive"))
    )
    (net (code "10") (name "Net-(C24-Pad1)") (class "Default")
      (node (ref "C24") (pin "1") (pinfunction "1_1") (pintype "passive"))
      (node (ref "CONN6") (pin "VBUS") (pinfunction "VBUS_VBUS") (pintype "power_in"))
      (node (ref "FB5") (pin "1") (pinfunction "1_1") (pintype "passive"))
    )
    (net (code "11") (name "Net-(C28-Pad1)") (class "Default")
      (node (ref "C28") (pin "1") (pinfunction "1_1") (pintype "passive"))
      (node (ref "CONN7") (pin "VBUS") (pinfunction "VBUS_VBUS") (pintype "power_in"))
      (node (ref "FB6") (pin "1") (pinfunction "1_1") (pintype "passive"))
    )
    (net (code "12") (name "Net-(CONN1-PadVBUS)") (class "Default")
      (node (ref "CONN1") (pin "VBUS") (pinfunction "VBUS_VBUS") (pintype "power_in"))
      (node (ref "F1") (pin "2") (pinfunction "2_2") (pintype "passive"))
    )
    (net (code "13") (name "Net-(CONN4-D+)") (class "Default")
      (node (ref "BR1") (pin "2") (pinfunction "2_2") (pintype "bidirectional"))
      (node (ref "CONN4") (pin "SIG2") (pinfunction "D+_SIG2") (pintype "bidirectional"))
      (node (ref "L1") (pin "2") (pinfunction "2_2") (pintype "bidirectional"))
      (node (ref "R7") (pin "1") (pinfunction "1_1") (pintype "passive"))
    )
    (net (code "14") (name "Net-(CONN4-D-)") (class "Default")
      (node (ref "BR1") (pin "4") (pinfunction "4_4") (pintype "bidirectional"))
      (node (ref "CONN4") (pin "SIG1") (pinfunction "D-_SIG1") (pintype "bidirectional"))
      (node (ref "L1") (pin "3") (pinfunction "3_3") (pintype "bidirectional"))
      (node (ref "R5") (pin "2") (pinfunction "2_2") (pintype "passive"))
    )
    (net (code "15") (name "Net-(CONN5-D+)") (class "Default")
      (node (ref "BR2") (pin "2") (pinfunction "2_2") (pintype "bidirectional"))
      (node (ref "CONN5") (pin "SIG2") (pinfunction "D+_SIG2") (pintype "bidirectional"))
      (node (ref "L2") (pin "2") (pinfunction "2_2") (pintype "bidirectional"))
      (node (ref "R14") (pin "1") (pinfunction "1_1") (pintype "passive"))
    )
    (net (code "16") (name "Net-(CONN5-D-)") (class "Default")
      (node (ref "BR2") (pin "4") (pinfunction "4_4") (pintype "bidirectional"))
      (node (ref "CONN5") (pin "SIG1") (pinfunction "D-_SIG1") (pintype "bidirectional"))
      (node (ref "L2") (pin "3") (pinfunction "3_3") (pintype "bidirectional"))
      (node (ref "R4") (pin "2") (pinfunction "2_2") (pintype "passive"))
    )
    (net (code "17") (name "Net-(CONN6-D+)") (class "Default")
      (node (ref "BR3") (pin "2") (pinfunction "2_2") (pintype "bidirectional"))
      (node (ref "CONN6") (pin "SIG2") (pinfunction "D+_SIG2") (pintype "bidirectional"))
      (node (ref "L3") (pin "2") (pinfunction "2_2") (pintype "bidirectional"))
      (node (ref "R15") (pin "1") (pinfunction "1_1") (pintype "passive"))
    )
    (net (code "18") (name "Net-(CONN6-D-)") (class "Default")
      (node (ref "BR3") (pin "4") (pinfunction "4_4") (pintype "bidirectional"))
      (node (ref "CONN6") (pin "SIG1") (pinfunction "D-_SIG1") (pintype "bidirectional"))
      (node (ref "L3") (pin "3") (pinfunction "3_3") (pintype "bidirectional"))
      (node (ref "R3") (pin "2") (pinfunction "2_2") (pintype "passive"))
    )
    (net (code "19") (name "Net-(CONN7-D+)") (class "Default")
      (node (ref "BR4") (pin "2") (pinfunction "2_2") (pintype "bidirectional"))
      (node (ref "CONN7") (pin "SIG2") (pinfunction "D+_SIG2") (pintype "bidirectional"))
      (node (ref "L4") (pin "2") (pinfunction "2_2") (pintype "bidirectional"))
      (node (ref "R16") (pin "1") (pinfunction "1_1") (pintype "passive"))
    )
    (net (code "20") (name "Net-(CONN7-D-)") (class "Default")
      (node (ref "BR4") (pin "4") (pinfunction "4_4") (pintype "bidirectional"))
      (node (ref "CONN7") (pin "SIG1") (pinfunction "D-_SIG1") (pintype "bidirectional"))
      (node (ref "L4") (pin "3") (pinfunction "3_3") (pintype "bidirectional"))
      (node (ref "R2") (pin "2") (pinfunction "2_2") (pintype "passive"))
    )
    (net (code "21") (name "Net-(D1-1)") (class "Default")
      (node (ref "CONN3") (pin "1") (pinfunction "1_1") (pintype "bidirectional"))
      (node (ref "D1") (pin "P$1") (pinfunction "1_P$1") (pintype "passive"))
    )
    (net (code "22") (name "Net-(LED2-PadA)") (class "Default")
      (node (ref "LED2") (pin "A") (pinfunction "A_A") (pintype "passive"))
      (node (ref "R31") (pin "2") (pinfunction "2_2") (pintype "passive"))
    )
    (net (code "23") (name "Net-(U1-CRFILT)") (class "Default")
      (node (ref "C44") (pin "1") (pinfunction "1_1") (pintype "passive"))
      (node (ref "C45") (pin "1") (pinfunction "1_1") (pintype "passive"))
      (node (ref "U1") (pin "14") (pinfunction "CRFILT_14") (pintype "bidirectional"))
    )
    (net (code "24") (name "Net-(U1-HS_IND{slash}CFG_SEL1)") (class "Default")
      (node (ref "R35") (pin "2") (pinfunction "2_2") (pintype "passive"))
      (node (ref "R38") (pin "1") (pinfunction "1_1") (pintype "passive"))
      (node (ref "U1") (pin "25") (pinfunction "HS_IND/CFG_SEL1_25") (pintype "bidirectional"))
    )
    (net (code "25") (name "Net-(U1-PLLFILT)") (class "Default")
      (node (ref "C43") (pin "1") (pinfunction "1_1") (pintype "passive"))
      (node (ref "U1") (pin "34") (pinfunction "PLLFILT_34") (pintype "bidirectional"))
    )
    (net (code "26") (name "Net-(U1-RBIAS)") (class "Default")
      (node (ref "R34") (pin "2") (pinfunction "2_2") (pintype "passive"))
      (node (ref "U1") (pin "35") (pinfunction "RBIAS_35") (pintype "bidirectional"))
    )
    (net (code "27") (name "Net-(U1-SCL{slash}SMBCLK{slash}CFG_SEL0)") (class "Default")
      (node (ref "R36") (pin "2") (pinfunction "2_2") (pintype "passive"))
      (node (ref "R39") (pin "1") (pinfunction "1_1") (pintype "passive"))
      (node (ref "U1") (pin "24") (pinfunction "SCL/SMBCLK/CFG_SEL0_24") (pintype "bidirectional"))
      (node (ref "U2") (pin "6") (pinfunction "SCL_6") (pintype "bidirectional"))
    )
    (net (code "28") (name "Net-(U1-SDA{slash}SMBDATA{slash}NON_REM1)") (class "Default")
      (node (ref "R37") (pin "2") (pinfunction "2_2") (pintype "passive"))
      (node (ref "R40") (pin "1") (pinfunction "1_1") (pintype "passive"))
      (node (ref "U1") (pin "22") (pinfunction "SDA/SMBDATA/NON_REM1_22") (pintype "bidirectional"))
      (node (ref "U2") (pin "5") (pinfunction "SDA_5") (pintype "bidirectional"))
    )
    (net (code "29") (name "Net-(U1-SUSP_IND{slash}LOCAL_PWR{slash}NON_REM0)") (class "Default")
      (node (ref "R30") (pin "2") (pinfunction "2_2") (pintype "passive"))
      (node (ref "R31") (pin "1") (pinfunction "1_1") (pintype "passive"))
      (node (ref "U1") (pin "28") (pinfunction "SUSP_IND/LOCAL_PWR/NON_REM0_28") (pintype "bidirectional"))
    )
    (net (code "30") (name "Net-(U1-VBUS_DET)") (class "Default")
      (node (ref "R28") (pin "1") (pinfunction "1_1") (pintype "passive"))
      (node (ref "R29") (pin "1") (pinfunction "1_1") (pintype "passive"))
      (node (ref "U1") (pin "27") (pinfunction "VBUS_DET_27") (pintype "bidirectional"))
    )
    (net (code "31") (name "Net-(U3-NOISE_REDUCTION(NR))") (class "Default")
      (node (ref "C10") (pin "1") (pinfunction "1_1") (pintype "passive"))
      (node (ref "U3") (pin "1") (pinfunction "NOISE_REDUCTION(NR)_1") (pintype "bidirectional"))
    )
    (net (code "32") (name "OCS_N1") (class "Default")
      (node (ref "U1") (pin "13") (pinfunction "OCS_N1_13") (pintype "bidirectional"))
      (node (ref "U4") (pin "2") (pinfunction "FLGA_2") (pintype "open_collector"))
    )
    (net (code "33") (name "OCS_N2") (class "Default")
      (node (ref "U1") (pin "17") (pinfunction "OCS_N2_17") (pintype "bidirectional"))
      (node (ref "U4") (pin "3") (pinfunction "FLGB_3") (pintype "open_collector"))
    )
    (net (code "34") (name "OCS_N3") (class "Default")
      (node (ref "U1") (pin "19") (pinfunction "OCS_N3_19") (pintype "bidirectional"))
      (node (ref "U5") (pin "2") (pinfunction "FLGA_2") (pintype "open_collector"))
    )
    (net (code "35") (name "OCS_N4") (class "Default")
      (node (ref "U1") (pin "21") (pinfunction "OCS_N4_21") (pintype "bidirectional"))
      (node (ref "U5") (pin "3") (pinfunction "FLGB_3") (pintype "open_collector"))
    )
    (net (code "36") (name "PRTPWR1") (class "Default")
      (node (ref "U1") (pin "12") (pinfunction "PRTPWR1/BC_EN1_12") (pintype "bidirectional"))
      (node (ref "U4") (pin "1") (pinfunction "ENA_1") (pintype "input"))
    )
    (net (code "37") (name "PRTPWR2") (class "Default")
      (node (ref "U1") (pin "16") (pinfunction "PRTPWR2/BC_EN2_16") (pintype "bidirectional"))
      (node (ref "U4") (pin "4") (pinfunction "ENB_4") (pintype "input"))
    )
    (net (code "38") (name "PRTPWR3") (class "Default")
      (node (ref "U1") (pin "18") (pinfunction "PRTPWR3/BC_EN3_18") (pintype "bidirectional"))
      (node (ref "U5") (pin "1") (pinfunction "ENA_1") (pintype "input"))
    )
    (net (code "39") (name "PRTPWR4") (class "Default")
      (node (ref "U1") (pin "20") (pinfunction "PRTPWR4/BC_EN4_20") (pintype "bidirectional"))
      (node (ref "U5") (pin "4") (pinfunction "ENB_4") (pintype "input"))
    )
    (net (code "40") (name "PWR_IC_CN1_VBUS") (class "Default")
      (node (ref "BR1") (pin "3") (pinfunction "3_3") (pintype "bidirectional"))
      (node (ref "C23") (pin "+") (pinfunction "1_+") (pintype "passive"))
      (node (ref "C27") (pin "1") (pinfunction "1_1") (pintype "passive"))
      (node (ref "FB3") (pin "2") (pinfunction "2_2") (pintype "passive"))
      (node (ref "U4") (pin "8") (pinfunction "OUTA_8") (pintype "output"))
    )
    (net (code "41") (name "PWR_IC_CN2_VBUS") (class "Default")
      (node (ref "BR2") (pin "3") (pinfunction "3_3") (pintype "bidirectional"))
      (node (ref "C20") (pin "+") (pinfunction "1_+") (pintype "passive"))
      (node (ref "C21") (pin "1") (pinfunction "1_1") (pintype "passive"))
      (node (ref "FB4") (pin "2") (pinfunction "2_2") (pintype "passive"))
      (node (ref "U4") (pin "5") (pinfunction "OUTB_5") (pintype "output"))
    )
    (net (code "42") (name "PWR_IC_CN3_VBUS") (class "Default")
      (node (ref "BR3") (pin "3") (pinfunction "3_3") (pintype "bidirectional"))
      (node (ref "C25") (pin "+") (pinfunction "1_+") (pintype "passive"))
      (node (ref "C26") (pin "1") (pinfunction "1_1") (pintype "passive"))
      (node (ref "FB5") (pin "2") (pinfunction "2_2") (pintype "passive"))
      (node (ref "U5") (pin "8") (pinfunction "OUTA_8") (pintype "output"))
    )
    (net (code "43") (name "PWR_IC_CN4_VBUS") (class "Default")
      (node (ref "BR4") (pin "3") (pinfunction "3_3") (pintype "bidirectional"))
      (node (ref "C29") (pin "+") (pinfunction "1_+") (pintype "passive"))
      (node (ref "C30") (pin "1") (pinfunction "1_1") (pintype "passive"))
      (node (ref "FB6") (pin "2") (pinfunction "2_2") (pintype "passive"))
      (node (ref "U5") (pin "5") (pinfunction "OUTB_5") (pintype "output"))
    )
    (net (code "44") (name "RST_U2U_RST") (class "Default")
      (node (ref "C40") (pin "1") (pinfunction "1_1") (pintype "passive"))
      (node (ref "R32") (pin "2") (pinfunction "2_2") (pintype "passive"))
      (node (ref "U1") (pin "26") (pinfunction "RESET_N_26") (pintype "bidirectional"))
    )
    (net (code "45") (name "USBDN1_U2U_USBCON_N") (class "Default")
      (node (ref "L1") (pin "4") (pinfunction "4_4") (pintype "bidirectional"))
      (node (ref "R5") (pin "1") (pinfunction "1_1") (pintype "passive"))
      (node (ref "U1") (pin "1") (pinfunction "USBDM_DN1/PRT_DIS_M1_1") (pintype "bidirectional"))
    )
    (net (code "46") (name "USBDN1_U2U_USBCON_P") (class "Default")
      (node (ref "L1") (pin "1") (pinfunction "1_1") (pintype "bidirectional"))
      (node (ref "R7") (pin "2") (pinfunction "2_2") (pintype "passive"))
      (node (ref "U1") (pin "2") (pinfunction "USBDP_DN1/PRT_DIS_P1_2") (pintype "bidirectional"))
    )
    (net (code "47") (name "USBDN2_U2U_USBCON_N") (class "Default")
      (node (ref "L2") (pin "4") (pinfunction "4_4") (pintype "bidirectional"))
      (node (ref "R4") (pin "1") (pinfunction "1_1") (pintype "passive"))
      (node (ref "U1") (pin "3") (pinfunction "USBDM_DN2/PRT_DIS_M2_3") (pintype "bidirectional"))
    )
    (net (code "48") (name "USBDN2_U2U_USBCON_P") (class "Default")
      (node (ref "L2") (pin "1") (pinfunction "1_1") (pintype "bidirectional"))
      (node (ref "R14") (pin "2") (pinfunction "2_2") (pintype "passive"))
      (node (ref "U1") (pin "4") (pinfunction "USBDP_DN2/PRT_DIS_P2_4") (pintype "bidirectional"))
    )
    (net (code "49") (name "USBDN3_U2U_USBCON_N") (class "Default")
      (node (ref "L3") (pin "4") (pinfunction "4_4") (pintype "bidirectional"))
      (node (ref "R3") (pin "1") (pinfunction "1_1") (pintype "passive"))
      (node (ref "U1") (pin "6") (pinfunction "USBDM_DN3/PRT_DIS_M3_6") (pintype "bidirectional"))
    )
    (net (code "50") (name "USBDN3_U2U_USBCON_P") (class "Default")
      (node (ref "L3") (pin "1") (pinfunction "1_1") (pintype "bidirectional"))
      (node (ref "R15") (pin "2") (pinfunction "2_2") (pintype "passive"))
      (node (ref "U1") (pin "7") (pinfunction "USBDP_DN3/PRT_DIS_P3_7") (pintype "bidirectional"))
    )
    (net (code "51") (name "USBDN4_U2U_USBCON_N") (class "Default")
      (node (ref "L4") (pin "4") (pinfunction "4_4") (pintype "bidirectional"))
      (node (ref "R2") (pin "1") (pinfunction "1_1") (pintype "passive"))
      (node (ref "U1") (pin "8") (pinfunction "USBDM_DN4/PRT_DIS_M4_8") (pintype "bidirectional"))
    )
    (net (code "52") (name "USBDN4_U2U_USBCON_P") (class "Default")
      (node (ref "L4") (pin "1") (pinfunction "1_1") (pintype "bidirectional"))
      (node (ref "R16") (pin "2") (pinfunction "2_2") (pintype "passive"))
      (node (ref "U1") (pin "9") (pinfunction "USBDP_DN4/PRT_DIS_P4_9") (pintype "bidirectional"))
    )
    (net (code "53") (name "USBUP_USBCON_U2U_N") (class "Default")
      (node (ref "CONN2") (pin "D-") (pinfunction "D-_D-") (pintype "bidirectional"))
      (node (ref "U1") (pin "30") (pinfunction "USBDM_UP_30") (pintype "bidirectional"))
    )
    (net (code "54") (name "USBUP_USBCON_U2U_P") (class "Default")
      (node (ref "CONN2") (pin "D+") (pinfunction "D+_D+") (pintype "bidirectional"))
      (node (ref "U1") (pin "31") (pinfunction "USBDP_UP_31") (pintype "bidirectional"))
    )
    (net (code "55") (name "VBUS_UP") (class "Default")
      (node (ref "C22") (pin "1") (pinfunction "1_1") (pintype "passive"))
      (node (ref "C39") (pin "1") (pinfunction "1_1") (pintype "passive"))
      (node (ref "CONN2") (pin "VBUS") (pinfunction "VBUS_VBUS") (pintype "power_in"))
      (node (ref "D2") (pin "1") (pinfunction "1_1") (pintype "bidirectional"))
      (node (ref "R28") (pin "2") (pinfunction "2_2") (pintype "passive"))
    )
    (net (code "56") (name "VCC") (class "Default")
      (node (ref "C1") (pin "+") (pinfunction "1_+") (pintype "passive"))
      (node (ref "C7") (pin "1") (pinfunction "1_1") (pintype "passive"))
      (node (ref "D1") (pin "P$2") (pinfunction "3_P$2") (pintype "passive"))
      (node (ref "D2") (pin "3") (pinfunction "3_3") (pintype "bidirectional"))
      (node (ref "D3") (pin "1") (pinfunction "1_1") (pintype "bidirectional"))
      (node (ref "D3") (pin "2") (pinfunction "2_2") (pintype "bidirectional"))
      (node (ref "F1") (pin "1") (pinfunction "1_1") (pintype "passive"))
      (node (ref "U3") (pin "3") (pinfunction "ON/OFF_CONTROL_3") (pintype "bidirectional"))
      (node (ref "U3") (pin "4") (pinfunction "DC_INPUT(VIN)_4") (pintype "bidirectional"))
      (node (ref "U4") (pin "7") (pinfunction "IN_7") (pintype "input"))
      (node (ref "U5") (pin "7") (pinfunction "IN_7") (pintype "input"))
    )
  )
)
